# dengen1.net
KiCad netlist of a schematic drawn in EAGLE
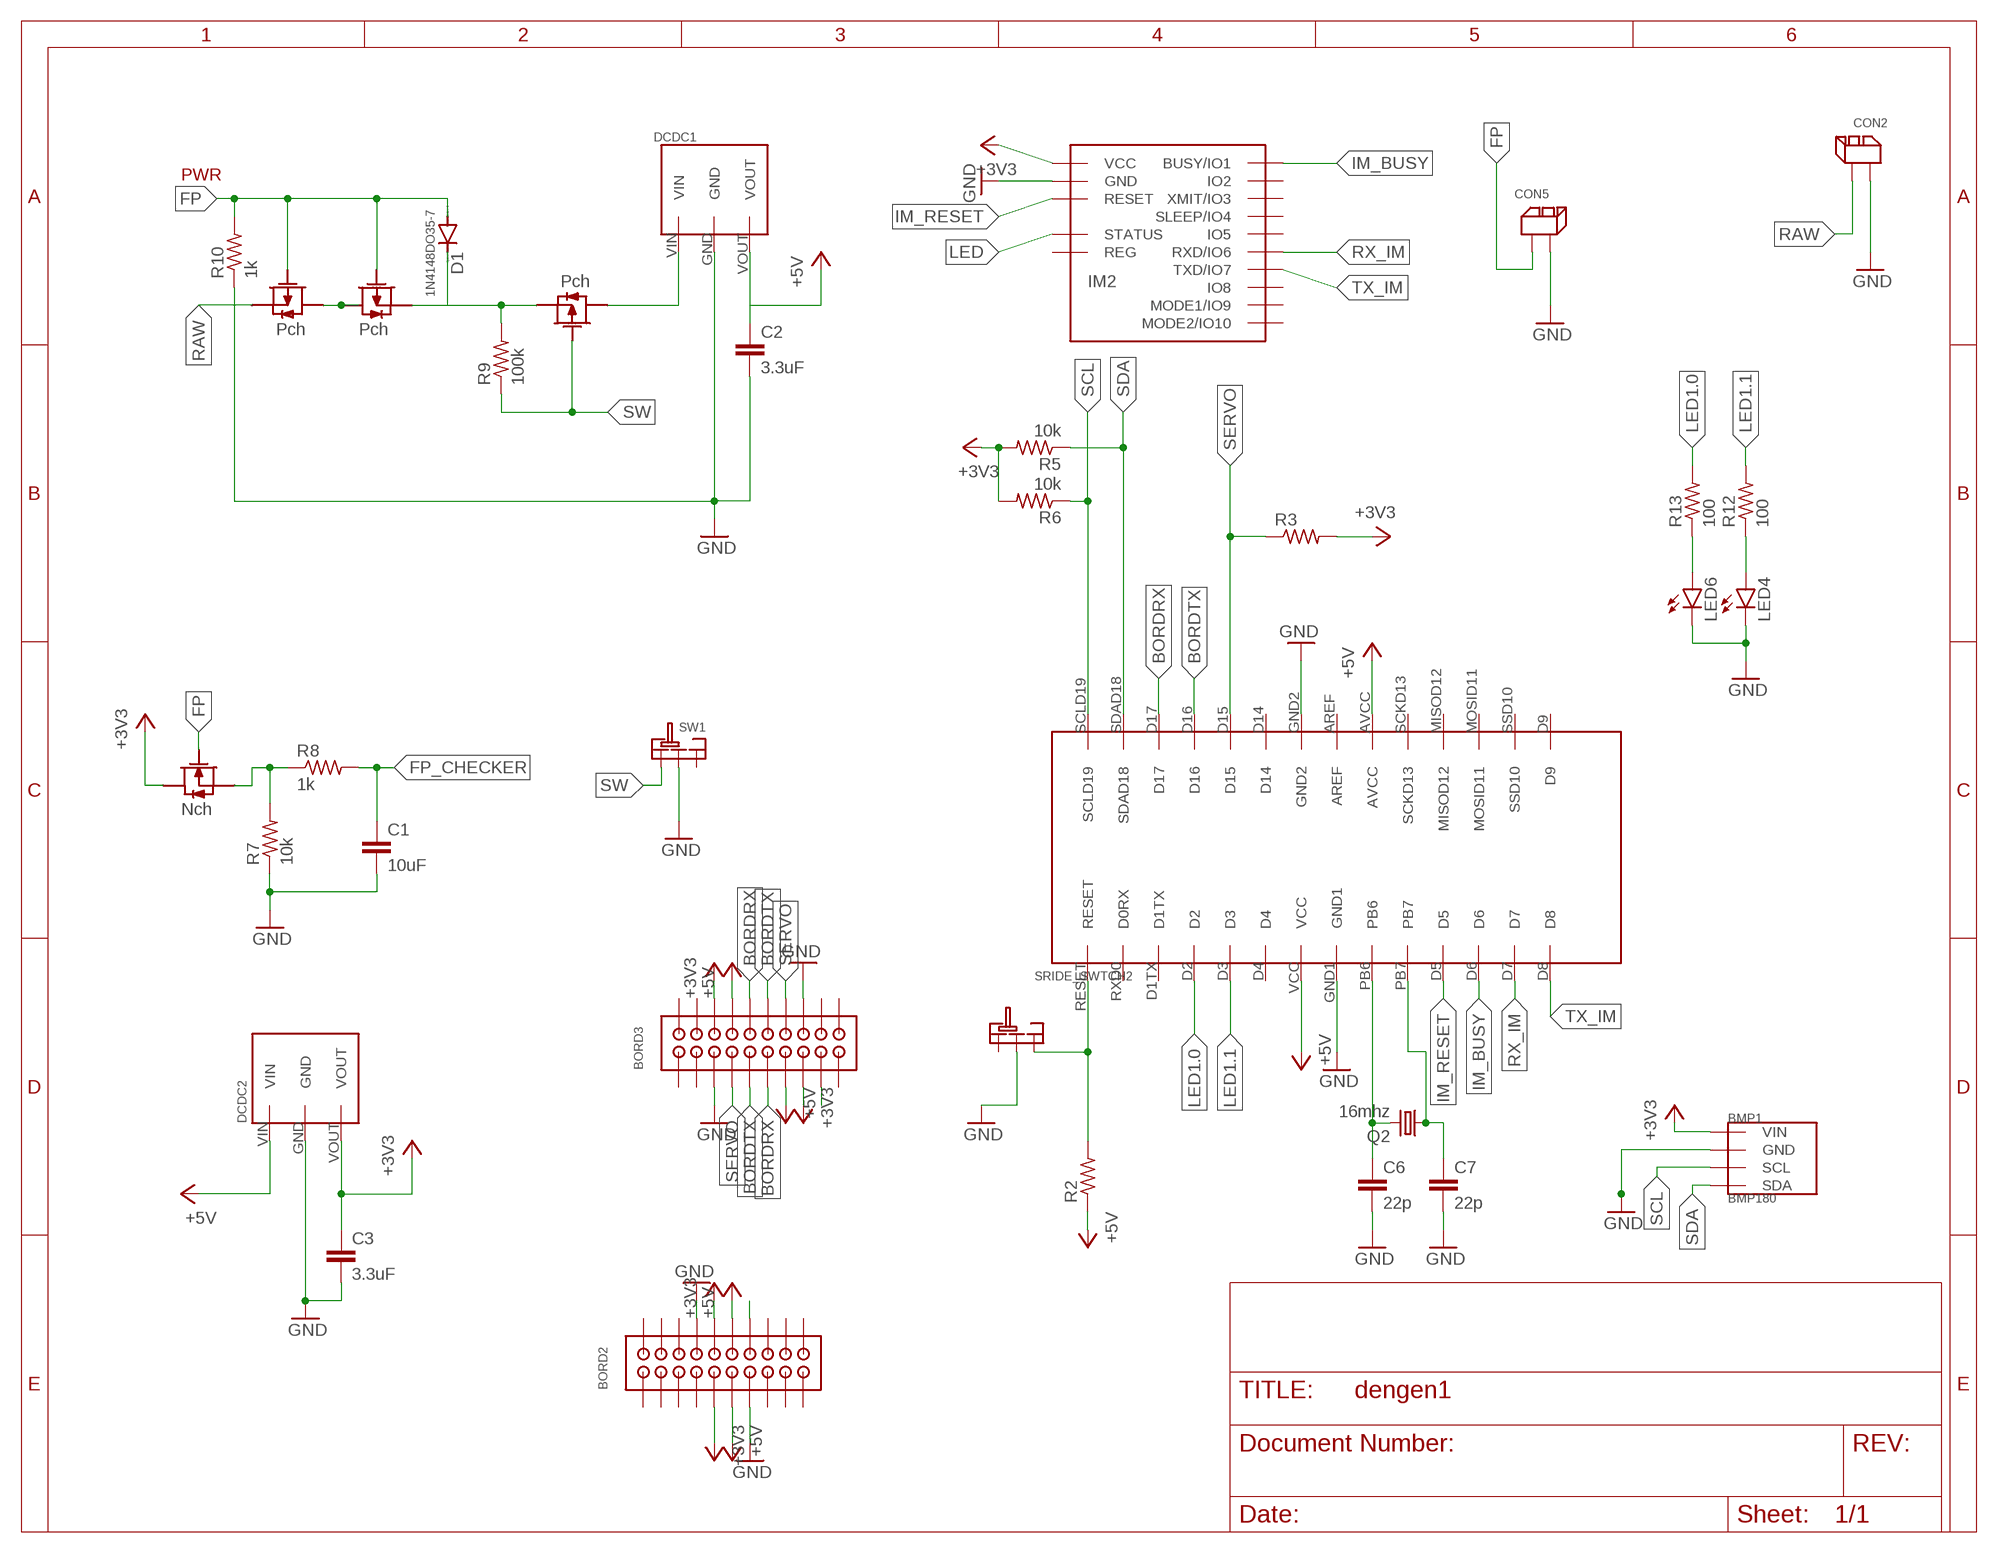
[diagram p0: schematic, sheet 1]

(export (version "E")
  (design (tool "Eeschema 10.0.6"))
  (components
    (comp (ref "BMP1")
      (value "BMP180")
      (footprint "eagle-import:GY-68")
      (libsource (lib "eagle-import") (part "BMP180"))
    )
    (comp (ref "BORD2")
      (value "2X10")
      (footprint "eagle-import:2X10")
      (libsource (lib "eagle-import") (part "2X10"))
    )
    (comp (ref "BORD3")
      (value "2X10")
      (footprint "eagle-import:2X10")
      (libsource (lib "eagle-import") (part "2X10"))
    )
    (comp (ref "C1")
      (value "10uF")
      (footprint "eagle-import:C025-024X044")
      (libsource (lib "eagle-import") (part "C-EU025-024X044"))
    )
    (comp (ref "C2")
      (value "3.3uF")
      (footprint "eagle-import:C025-024X044")
      (libsource (lib "eagle-import") (part "C-EU025-024X044"))
    )
    (comp (ref "C3")
      (value "3.3uF")
      (footprint "eagle-import:C025-024X044")
      (libsource (lib "eagle-import") (part "C-EU025-024X044"))
    )
    (comp (ref "C6")
      (value "22p")
      (footprint "eagle-import:C025-024X044")
      (libsource (lib "eagle-import") (part "C-EU025-024X044"))
    )
    (comp (ref "C7")
      (value "22p")
      (footprint "eagle-import:C025-024X044")
      (libsource (lib "eagle-import") (part "C-EU025-024X044"))
    )
    (comp (ref "CON2")
      (value "2PIN")
      (footprint "eagle-import:2PIN")
      (libsource (lib "eagle-import") (part "2PIN"))
    )
    (comp (ref "CON5")
      (value "2PIN")
      (footprint "eagle-import:2PIN")
      (libsource (lib "eagle-import") (part "2PIN"))
    )
    (comp (ref "D1")
      (value "1N4148DO35-7")
      (footprint "eagle-import:DO35-7")
      (libsource (lib "eagle-import") (part "1N4148DO35-7"))
    )
    (comp (ref "DCDC1")
      (value "5V1A_M78AR05-1")
      (footprint "eagle-import:5V1A_M78AR05-1")
      (libsource (lib "eagle-import") (part "5V1A_M78AR05-1"))
    )
    (comp (ref "DCDC2")
      (value "3.3V1A_M78AR033-1")
      (footprint "eagle-import:3.3V1A_M78AR033-1")
      (libsource (lib "eagle-import") (part "3.3V1A_M78AR033-1"))
    )
    (comp (ref "IM2")
      (value "IM920_IM920C")
      (footprint "eagle-import:IM920_IM920C")
      (libsource (lib "eagle-import") (part "IM920_IM920C"))
    )
    (comp (ref "LED4")
      (value "LED5MM")
      (footprint "eagle-import:LED5MM")
      (libsource (lib "eagle-import") (part "LED5MM"))
    )
    (comp (ref "LED6")
      (value "LED5MM")
      (footprint "eagle-import:LED5MM")
      (libsource (lib "eagle-import") (part "LED5MM"))
    )
    (comp (ref "Q2")
      (value "16mhz")
      (footprint "eagle-import:HC49_S")
      (libsource (lib "eagle-import") (part "CRYSTALHC49S"))
    )
    (comp (ref "R2")
      (value "R-US_0204/7")
      (footprint "eagle-import:0204_7")
      (libsource (lib "eagle-import") (part "R-US_0204/7"))
    )
    (comp (ref "R3")
      (value "R-US_0204/7")
      (footprint "eagle-import:0204_7")
      (libsource (lib "eagle-import") (part "R-US_0204/7"))
    )
    (comp (ref "R5")
      (value "10k")
      (footprint "eagle-import:0204_7")
      (libsource (lib "eagle-import") (part "R-US_0204/7"))
    )
    (comp (ref "R6")
      (value "10k")
      (footprint "eagle-import:0204_7")
      (libsource (lib "eagle-import") (part "R-US_0204/7"))
    )
    (comp (ref "R7")
      (value "10k")
      (footprint "eagle-import:0204_7")
      (libsource (lib "eagle-import") (part "R-US_0204/7"))
    )
    (comp (ref "R8")
      (value "1k")
      (footprint "eagle-import:0204_7")
      (libsource (lib "eagle-import") (part "R-US_0204/7"))
    )
    (comp (ref "R9")
      (value "100k")
      (footprint "eagle-import:0204_7")
      (libsource (lib "eagle-import") (part "R-US_0204/7"))
    )
    (comp (ref "R10")
      (value "1k")
      (footprint "eagle-import:0204_7")
      (libsource (lib "eagle-import") (part "R-US_0204/7"))
    )
    (comp (ref "R12")
      (value "100")
      (footprint "eagle-import:0204_7")
      (libsource (lib "eagle-import") (part "R-US_0204/7"))
    )
    (comp (ref "R13")
      (value "100")
      (footprint "eagle-import:0204_7")
      (libsource (lib "eagle-import") (part "R-US_0204/7"))
    )
    (comp (ref "SRIDE_SWTCH2")
      (value "SRIDE_SWITCH")
      (footprint "eagle-import:SRIDE_SWITCH")
      (libsource (lib "eagle-import") (part "SRIDE_SWITCH"))
    )
    (comp (ref "SW1")
      (value "SRIDE_SWITCH")
      (footprint "eagle-import:SRIDE_SWITCH")
      (libsource (lib "eagle-import") (part "SRIDE_SWITCH"))
    )
    (comp (ref "U$2")
      (value "2SJ681-PCH")
      (footprint "eagle-import:2SJ681")
      (libsource (lib "eagle-import") (part "2SJ681-PCH"))
    )
    (comp (ref "U$3")
      (value "2SK4017-NCH")
      (footprint "eagle-import:2SK4017")
      (libsource (lib "eagle-import") (part "2SK4017-NCH"))
    )
    (comp (ref "U$4")
      (value "2SJ681-PCH")
      (footprint "eagle-import:2SJ681")
      (libsource (lib "eagle-import") (part "2SJ681-PCH"))
    )
    (comp (ref "U$5")
      (value "2SJ681-PCH")
      (footprint "eagle-import:2SJ681")
      (libsource (lib "eagle-import") (part "2SJ681-PCH"))
    )
    (comp (ref "U$6")
      (value "ATMEGA238P")
      (footprint "eagle-import:ATMEGA328P")
      (libsource (lib "eagle-import") (part "ATMEGA238P"))
    )
  )
  (nets
    (net (code "1") (name "+3V3") (class "Default")
      (node (ref "BMP1") (pin "P1") (pinfunction "VIN_P1") (pintype "bidirectional"))
      (node (ref "BORD2") (pin "P$10") (pinfunction "P$10_P$10") (pintype "bidirectional"))
      (node (ref "BORD2") (pin "P$9") (pinfunction "P$9_P$9") (pintype "bidirectional"))
      (node (ref "BORD3") (pin "P$15") (pinfunction "P$15_P$15") (pintype "bidirectional"))
      (node (ref "BORD3") (pin "P$6") (pinfunction "P$6_P$6") (pintype "bidirectional"))
      (node (ref "C3") (pin "1") (pinfunction "1_1") (pintype "passive"))
      (node (ref "DCDC2") (pin "VOUT") (pinfunction "VOUT_VOUT") (pintype "bidirectional"))
      (node (ref "IM2") (pin "$P17") (pinfunction "VCC_$P17") (pintype "bidirectional"))
      (node (ref "R3") (pin "2") (pinfunction "2_2") (pintype "passive"))
      (node (ref "R5") (pin "2") (pinfunction "2_2") (pintype "passive"))
      (node (ref "R6") (pin "2") (pinfunction "2_2") (pintype "passive"))
      (node (ref "U$3") (pin "DRAIN") (pinfunction "DRAIN_DRAIN") (pintype "bidirectional"))
    )
    (net (code "2") (name "+5V") (class "Default")
      (node (ref "BORD2") (pin "P$11") (pinfunction "P$11_P$11") (pintype "bidirectional"))
      (node (ref "BORD2") (pin "P$12") (pinfunction "P$12_P$12") (pintype "bidirectional"))
      (node (ref "BORD3") (pin "P$13") (pinfunction "P$13_P$13") (pintype "bidirectional"))
      (node (ref "BORD3") (pin "P$8") (pinfunction "P$8_P$8") (pintype "bidirectional"))
      (node (ref "C2") (pin "1") (pinfunction "1_1") (pintype "passive"))
      (node (ref "DCDC1") (pin "VOUT") (pinfunction "VOUT_VOUT") (pintype "bidirectional"))
      (node (ref "DCDC2") (pin "VIN") (pinfunction "VIN_VIN") (pintype "bidirectional"))
      (node (ref "R2") (pin "1") (pinfunction "1_1") (pintype "passive"))
      (node (ref "U$6") (pin "AVCC") (pinfunction "AVCC_AVCC") (pintype "bidirectional"))
      (node (ref "U$6") (pin "VCC") (pinfunction "VCC_VCC") (pintype "bidirectional"))
    )
    (net (code "3") (name "BORDRX") (class "Default")
      (node (ref "BORD3") (pin "P$10") (pinfunction "P$10_P$10") (pintype "bidirectional"))
      (node (ref "BORD3") (pin "P$11") (pinfunction "P$11_P$11") (pintype "bidirectional"))
      (node (ref "U$6") (pin "D17") (pinfunction "D17_D17") (pintype "bidirectional"))
    )
    (net (code "4") (name "BORDTX") (class "Default")
      (node (ref "BORD3") (pin "P$12") (pinfunction "P$12_P$12") (pintype "bidirectional"))
      (node (ref "BORD3") (pin "P$9") (pinfunction "P$9_P$9") (pintype "bidirectional"))
      (node (ref "U$6") (pin "D16") (pinfunction "D16_D16") (pintype "bidirectional"))
    )
    (net (code "5") (name "FP") (class "Default")
      (node (ref "CON5") (pin "P$1") (pinfunction "P$1_P$1") (pintype "bidirectional"))
      (node (ref "D1") (pin "A") (pinfunction "A_A") (pintype "passive"))
      (node (ref "R10") (pin "2") (pinfunction "2_2") (pintype "passive"))
      (node (ref "U$2") (pin "GATE") (pinfunction "GATE_GATE") (pintype "bidirectional"))
      (node (ref "U$3") (pin "GATE") (pinfunction "GATE_GATE") (pintype "bidirectional"))
      (node (ref "U$4") (pin "GATE") (pinfunction "GATE_GATE") (pintype "bidirectional"))
    )
    (net (code "6") (name "FP_CHECKER") (class "Default")
      (node (ref "C1") (pin "1") (pinfunction "1_1") (pintype "passive"))
      (node (ref "R8") (pin "2") (pinfunction "2_2") (pintype "passive"))
    )
    (net (code "7") (name "GND") (class "Default")
      (node (ref "BMP1") (pin "P2") (pinfunction "GND_P2") (pintype "bidirectional"))
      (node (ref "BORD2") (pin "P$13") (pinfunction "P$13_P$13") (pintype "bidirectional"))
      (node (ref "BORD2") (pin "P$8") (pinfunction "P$8_P$8") (pintype "bidirectional"))
      (node (ref "BORD3") (pin "P$16") (pinfunction "P$16_P$16") (pintype "bidirectional"))
      (node (ref "BORD3") (pin "P$5") (pinfunction "P$5_P$5") (pintype "bidirectional"))
      (node (ref "C1") (pin "2") (pinfunction "2_2") (pintype "passive"))
      (node (ref "C2") (pin "2") (pinfunction "2_2") (pintype "passive"))
      (node (ref "C3") (pin "2") (pinfunction "2_2") (pintype "passive"))
      (node (ref "C6") (pin "2") (pinfunction "2_2") (pintype "passive"))
      (node (ref "C7") (pin "2") (pinfunction "2_2") (pintype "passive"))
      (node (ref "CON2") (pin "P$1") (pinfunction "P$1_P$1") (pintype "bidirectional"))
      (node (ref "CON5") (pin "P$2") (pinfunction "P$2_P$2") (pintype "bidirectional"))
      (node (ref "DCDC1") (pin "GND") (pinfunction "GND_GND") (pintype "bidirectional"))
      (node (ref "DCDC2") (pin "GND") (pinfunction "GND_GND") (pintype "bidirectional"))
      (node (ref "IM2") (pin "$P18") (pinfunction "GND_$P18") (pintype "bidirectional"))
      (node (ref "LED4") (pin "K") (pinfunction "C_K") (pintype "passive"))
      (node (ref "LED6") (pin "K") (pinfunction "C_K") (pintype "passive"))
      (node (ref "R10") (pin "1") (pinfunction "1_1") (pintype "passive"))
      (node (ref "R7") (pin "1") (pinfunction "1_1") (pintype "passive"))
      (node (ref "SRIDE_SWTCH2") (pin "LR") (pinfunction "LR_LR") (pintype "bidirectional"))
      (node (ref "SW1") (pin "LR") (pinfunction "LR_LR") (pintype "bidirectional"))
      (node (ref "U$6") (pin "GND1") (pinfunction "GND1_GND1") (pintype "bidirectional"))
      (node (ref "U$6") (pin "GND2") (pinfunction "GND2_GND2") (pintype "bidirectional"))
    )
    (net (code "8") (name "IM_BUSY") (class "Default")
      (node (ref "IM2") (pin "$P1") (pinfunction "BUSY/IO1_$P1") (pintype "bidirectional"))
      (node (ref "U$6") (pin "D6") (pinfunction "D6_D6") (pintype "bidirectional"))
    )
    (net (code "9") (name "IM_RESET") (class "Default")
      (node (ref "IM2") (pin "$P19") (pinfunction "RESET_$P19") (pintype "bidirectional"))
      (node (ref "U$6") (pin "D5") (pinfunction "D5_D5") (pintype "bidirectional"))
    )
    (net (code "10") (name "LED") (class "Default")
      (node (ref "IM2") (pin "$P15") (pinfunction "STATUS_$P15") (pintype "bidirectional"))
    )
    (net (code "11") (name "LED1.0") (class "Default")
      (node (ref "R13") (pin "2") (pinfunction "2_2") (pintype "passive"))
      (node (ref "U$6") (pin "D2") (pinfunction "D2_D2") (pintype "bidirectional"))
    )
    (net (code "12") (name "LED1.1") (class "Default")
      (node (ref "R12") (pin "2") (pinfunction "2_2") (pintype "passive"))
      (node (ref "U$6") (pin "D3") (pinfunction "D3_D3") (pintype "bidirectional"))
    )
    (net (code "13") (name "Net-(C6-Pad1)") (class "Default")
      (node (ref "C6") (pin "1") (pinfunction "1_1") (pintype "passive"))
      (node (ref "Q2") (pin "2") (pinfunction "2_2") (pintype "passive"))
      (node (ref "U$6") (pin "PB6") (pinfunction "PB6_PB6") (pintype "bidirectional"))
    )
    (net (code "14") (name "Net-(C7-Pad1)") (class "Default")
      (node (ref "C7") (pin "1") (pinfunction "1_1") (pintype "passive"))
      (node (ref "Q2") (pin "1") (pinfunction "1_1") (pintype "passive"))
      (node (ref "U$6") (pin "PB7") (pinfunction "PB7_PB7") (pintype "bidirectional"))
    )
    (net (code "15") (name "Net-(D1-PadC)") (class "Default")
      (node (ref "D1") (pin "C") (pinfunction "C_C") (pintype "passive"))
      (node (ref "R9") (pin "2") (pinfunction "2_2") (pintype "passive"))
      (node (ref "U$4") (pin "SOURCE") (pinfunction "SOURCE_SOURCE") (pintype "bidirectional"))
      (node (ref "U$5") (pin "SOURCE") (pinfunction "SOURCE_SOURCE") (pintype "bidirectional"))
    )
    (net (code "16") (name "Net-(DCDC1-PadVIN)") (class "Default")
      (node (ref "DCDC1") (pin "VIN") (pinfunction "VIN_VIN") (pintype "bidirectional"))
      (node (ref "U$5") (pin "DRAIN") (pinfunction "DRAIN_DRAIN") (pintype "bidirectional"))
    )
    (net (code "17") (name "Net-(LED4-PadA)") (class "Default")
      (node (ref "LED4") (pin "A") (pinfunction "A_A") (pintype "passive"))
      (node (ref "R12") (pin "1") (pinfunction "1_1") (pintype "passive"))
    )
    (net (code "18") (name "Net-(LED6-PadA)") (class "Default")
      (node (ref "LED6") (pin "A") (pinfunction "A_A") (pintype "passive"))
      (node (ref "R13") (pin "1") (pinfunction "1_1") (pintype "passive"))
    )
    (net (code "19") (name "Net-(R2-Pad2)") (class "Default")
      (node (ref "R2") (pin "2") (pinfunction "2_2") (pintype "passive"))
      (node (ref "SRIDE_SWTCH2") (pin "R") (pinfunction "R_R") (pintype "bidirectional"))
      (node (ref "U$6") (pin "RESET") (pinfunction "RESET_RESET") (pintype "bidirectional"))
    )
    (net (code "20") (name "Net-(R7-Pad2)") (class "Default")
      (node (ref "R7") (pin "2") (pinfunction "2_2") (pintype "passive"))
      (node (ref "R8") (pin "1") (pinfunction "1_1") (pintype "passive"))
      (node (ref "U$3") (pin "SOURCE") (pinfunction "SOURCE_SOURCE") (pintype "bidirectional"))
    )
    (net (code "21") (name "Net-(U$2-PadDRAIN)") (class "Default")
      (node (ref "U$2") (pin "DRAIN") (pinfunction "DRAIN_DRAIN") (pintype "bidirectional"))
      (node (ref "U$4") (pin "DRAIN") (pinfunction "DRAIN_DRAIN") (pintype "bidirectional"))
    )
    (net (code "22") (name "RAW") (class "Default")
      (node (ref "CON2") (pin "P$2") (pinfunction "P$2_P$2") (pintype "bidirectional"))
      (node (ref "U$2") (pin "SOURCE") (pinfunction "SOURCE_SOURCE") (pintype "bidirectional"))
    )
    (net (code "23") (name "RX_IM") (class "Default")
      (node (ref "IM2") (pin "$P6") (pinfunction "RXD/IO6_$P6") (pintype "bidirectional"))
      (node (ref "U$6") (pin "D7") (pinfunction "D7_D7") (pintype "bidirectional"))
    )
    (net (code "24") (name "SCL") (class "Default")
      (node (ref "BMP1") (pin "P3") (pinfunction "SCL_P3") (pintype "bidirectional"))
      (node (ref "R6") (pin "1") (pinfunction "1_1") (pintype "passive"))
      (node (ref "U$6") (pin "SCLD19") (pinfunction "SCLD19_SCLD19") (pintype "bidirectional"))
    )
    (net (code "25") (name "SDA") (class "Default")
      (node (ref "BMP1") (pin "P4") (pinfunction "SDA_P4") (pintype "bidirectional"))
      (node (ref "R5") (pin "1") (pinfunction "1_1") (pintype "passive"))
      (node (ref "U$6") (pin "SDAD18") (pinfunction "SDAD18_SDAD18") (pintype "bidirectional"))
    )
    (net (code "26") (name "SERVO") (class "Default")
      (node (ref "BORD3") (pin "P$14") (pinfunction "P$14_P$14") (pintype "bidirectional"))
      (node (ref "BORD3") (pin "P$7") (pinfunction "P$7_P$7") (pintype "bidirectional"))
      (node (ref "R3") (pin "1") (pinfunction "1_1") (pintype "passive"))
      (node (ref "U$6") (pin "D15") (pinfunction "D15_D15") (pintype "bidirectional"))
    )
    (net (code "27") (name "SW") (class "Default")
      (node (ref "R9") (pin "1") (pinfunction "1_1") (pintype "passive"))
      (node (ref "SW1") (pin "L") (pinfunction "L_L") (pintype "bidirectional"))
      (node (ref "U$5") (pin "GATE") (pinfunction "GATE_GATE") (pintype "bidirectional"))
    )
    (net (code "28") (name "TX_IM") (class "Default")
      (node (ref "IM2") (pin "$P7") (pinfunction "TXD/IO7_$P7") (pintype "bidirectional"))
      (node (ref "U$6") (pin "D8") (pinfunction "D8_D8") (pintype "bidirectional"))
    )
    (net (code "29") (name "unconnected-(BORD2-PadP$1)") (class "Default")
      (node (ref "BORD2") (pin "P$1") (pinfunction "P$1_P$1") (pintype "bidirectional"))
    )
    (net (code "30") (name "unconnected-(BORD2-PadP$2)") (class "Default")
      (node (ref "BORD2") (pin "P$2") (pinfunction "P$2_P$2") (pintype "bidirectional"))
    )
    (net (code "31") (name "unconnected-(BORD2-PadP$3)") (class "Default")
      (node (ref "BORD2") (pin "P$3") (pinfunction "P$3_P$3") (pintype "bidirectional"))
    )
    (net (code "32") (name "unconnected-(BORD2-PadP$4)") (class "Default")
      (node (ref "BORD2") (pin "P$4") (pinfunction "P$4_P$4") (pintype "bidirectional"))
    )
    (net (code "33") (name "unconnected-(BORD2-PadP$5)") (class "Default")
      (node (ref "BORD2") (pin "P$5") (pinfunction "P$5_P$5") (pintype "bidirectional"))
    )
    (net (code "34") (name "unconnected-(BORD2-PadP$6)") (class "Default")
      (node (ref "BORD2") (pin "P$6") (pinfunction "P$6_P$6") (pintype "bidirectional"))
    )
    (net (code "35") (name "unconnected-(BORD2-PadP$7)") (class "Default")
      (node (ref "BORD2") (pin "P$7") (pinfunction "P$7_P$7") (pintype "bidirectional"))
    )
    (net (code "36") (name "unconnected-(BORD2-PadP$14)") (class "Default")
      (node (ref "BORD2") (pin "P$14") (pinfunction "P$14_P$14") (pintype "bidirectional"))
    )
    (net (code "37") (name "unconnected-(BORD2-PadP$15)") (class "Default")
      (node (ref "BORD2") (pin "P$15") (pinfunction "P$15_P$15") (pintype "bidirectional"))
    )
    (net (code "38") (name "unconnected-(BORD2-PadP$16)") (class "Default")
      (node (ref "BORD2") (pin "P$16") (pinfunction "P$16_P$16") (pintype "bidirectional"))
    )
    (net (code "39") (name "unconnected-(BORD2-PadP$17)") (class "Default")
      (node (ref "BORD2") (pin "P$17") (pinfunction "P$17_P$17") (pintype "bidirectional"))
    )
    (net (code "40") (name "unconnected-(BORD2-PadP$18)") (class "Default")
      (node (ref "BORD2") (pin "P$18") (pinfunction "P$18_P$18") (pintype "bidirectional"))
    )
    (net (code "41") (name "unconnected-(BORD2-PadP$19)") (class "Default")
      (node (ref "BORD2") (pin "P$19") (pinfunction "P$19_P$19") (pintype "bidirectional"))
    )
    (net (code "42") (name "unconnected-(BORD2-PadP$20)") (class "Default")
      (node (ref "BORD2") (pin "P$20") (pinfunction "P$20_P$20") (pintype "bidirectional"))
    )
    (net (code "43") (name "unconnected-(BORD3-PadP$1)") (class "Default")
      (node (ref "BORD3") (pin "P$1") (pinfunction "P$1_P$1") (pintype "bidirectional"))
    )
    (net (code "44") (name "unconnected-(BORD3-PadP$2)") (class "Default")
      (node (ref "BORD3") (pin "P$2") (pinfunction "P$2_P$2") (pintype "bidirectional"))
    )
    (net (code "45") (name "unconnected-(BORD3-PadP$3)") (class "Default")
      (node (ref "BORD3") (pin "P$3") (pinfunction "P$3_P$3") (pintype "bidirectional"))
    )
    (net (code "46") (name "unconnected-(BORD3-PadP$4)") (class "Default")
      (node (ref "BORD3") (pin "P$4") (pinfunction "P$4_P$4") (pintype "bidirectional"))
    )
    (net (code "47") (name "unconnected-(BORD3-PadP$17)") (class "Default")
      (node (ref "BORD3") (pin "P$17") (pinfunction "P$17_P$17") (pintype "bidirectional"))
    )
    (net (code "48") (name "unconnected-(BORD3-PadP$18)") (class "Default")
      (node (ref "BORD3") (pin "P$18") (pinfunction "P$18_P$18") (pintype "bidirectional"))
    )
    (net (code "49") (name "unconnected-(BORD3-PadP$19)") (class "Default")
      (node (ref "BORD3") (pin "P$19") (pinfunction "P$19_P$19") (pintype "bidirectional"))
    )
    (net (code "50") (name "unconnected-(BORD3-PadP$20)") (class "Default")
      (node (ref "BORD3") (pin "P$20") (pinfunction "P$20_P$20") (pintype "bidirectional"))
    )
    (net (code "51") (name "unconnected-(IM2-IO2-Pad$P2)") (class "Default")
      (node (ref "IM2") (pin "$P2") (pinfunction "IO2_$P2") (pintype "bidirectional"))
    )
    (net (code "52") (name "unconnected-(IM2-IO5-Pad$P5)") (class "Default")
      (node (ref "IM2") (pin "$P5") (pinfunction "IO5_$P5") (pintype "bidirectional"))
    )
    (net (code "53") (name "unconnected-(IM2-IO8-Pad$P8)") (class "Default")
      (node (ref "IM2") (pin "$P8") (pinfunction "IO8_$P8") (pintype "bidirectional"))
    )
    (net (code "54") (name "unconnected-(IM2-MODE1{slash}IO9-Pad$P9)") (class "Default")
      (node (ref "IM2") (pin "$P9") (pinfunction "MODE1/IO9_$P9") (pintype "bidirectional"))
    )
    (net (code "55") (name "unconnected-(IM2-MODE2{slash}IO10-Pad$P10)") (class "Default")
      (node (ref "IM2") (pin "$P10") (pinfunction "MODE2/IO10_$P10") (pintype "bidirectional"))
    )
    (net (code "56") (name "unconnected-(IM2-REG-Pad$P16)") (class "Default")
      (node (ref "IM2") (pin "$P16") (pinfunction "REG_$P16") (pintype "bidirectional"))
    )
    (net (code "57") (name "unconnected-(IM2-SLEEP{slash}IO4-Pad$P4)") (class "Default")
      (node (ref "IM2") (pin "$P4") (pinfunction "SLEEP/IO4_$P4") (pintype "bidirectional"))
    )
    (net (code "58") (name "unconnected-(IM2-XMIT{slash}IO3-Pad$P3)") (class "Default")
      (node (ref "IM2") (pin "$P3") (pinfunction "XMIT/IO3_$P3") (pintype "bidirectional"))
    )
    (net (code "59") (name "unconnected-(SRIDE_SWTCH2-PadL)") (class "Default")
      (node (ref "SRIDE_SWTCH2") (pin "L") (pinfunction "L_L") (pintype "bidirectional"))
    )
    (net (code "60") (name "unconnected-(SW1-PadR)") (class "Default")
      (node (ref "SW1") (pin "R") (pinfunction "R_R") (pintype "bidirectional"))
    )
    (net (code "61") (name "unconnected-(U$6-D0RX-PadRXD0)") (class "Default")
      (node (ref "U$6") (pin "RXD0") (pinfunction "D0RX_RXD0") (pintype "bidirectional"))
    )
    (net (code "62") (name "unconnected-(U$6-PadAREF)") (class "Default")
      (node (ref "U$6") (pin "AREF") (pinfunction "AREF_AREF") (pintype "bidirectional"))
    )
    (net (code "63") (name "unconnected-(U$6-PadD1TX)") (class "Default")
      (node (ref "U$6") (pin "D1TX") (pinfunction "D1TX_D1TX") (pintype "bidirectional"))
    )
    (net (code "64") (name "unconnected-(U$6-PadD4)") (class "Default")
      (node (ref "U$6") (pin "D4") (pinfunction "D4_D4") (pintype "bidirectional"))
    )
    (net (code "65") (name "unconnected-(U$6-PadD9)") (class "Default")
      (node (ref "U$6") (pin "D9") (pinfunction "D9_D9") (pintype "bidirectional"))
    )
    (net (code "66") (name "unconnected-(U$6-PadD14)") (class "Default")
      (node (ref "U$6") (pin "D14") (pinfunction "D14_D14") (pintype "bidirectional"))
    )
    (net (code "67") (name "unconnected-(U$6-PadMISOD12)") (class "Default")
      (node (ref "U$6") (pin "MISOD12") (pinfunction "MISOD12_MISOD12") (pintype "bidirectional"))
    )
    (net (code "68") (name "unconnected-(U$6-PadMOSID11)") (class "Default")
      (node (ref "U$6") (pin "MOSID11") (pinfunction "MOSID11_MOSID11") (pintype "bidirectional"))
    )
    (net (code "69") (name "unconnected-(U$6-PadSCKD13)") (class "Default")
      (node (ref "U$6") (pin "SCKD13") (pinfunction "SCKD13_SCKD13") (pintype "bidirectional"))
    )
    (net (code "70") (name "unconnected-(U$6-PadSSD10)") (class "Default")
      (node (ref "U$6") (pin "SSD10") (pinfunction "SSD10_SSD10") (pintype "bidirectional"))
    )
  )
)
